# SCH_HOME-AUTOMATION_2025-03-31.net
KiCad netlist of a schematic drawn in EasyEDA
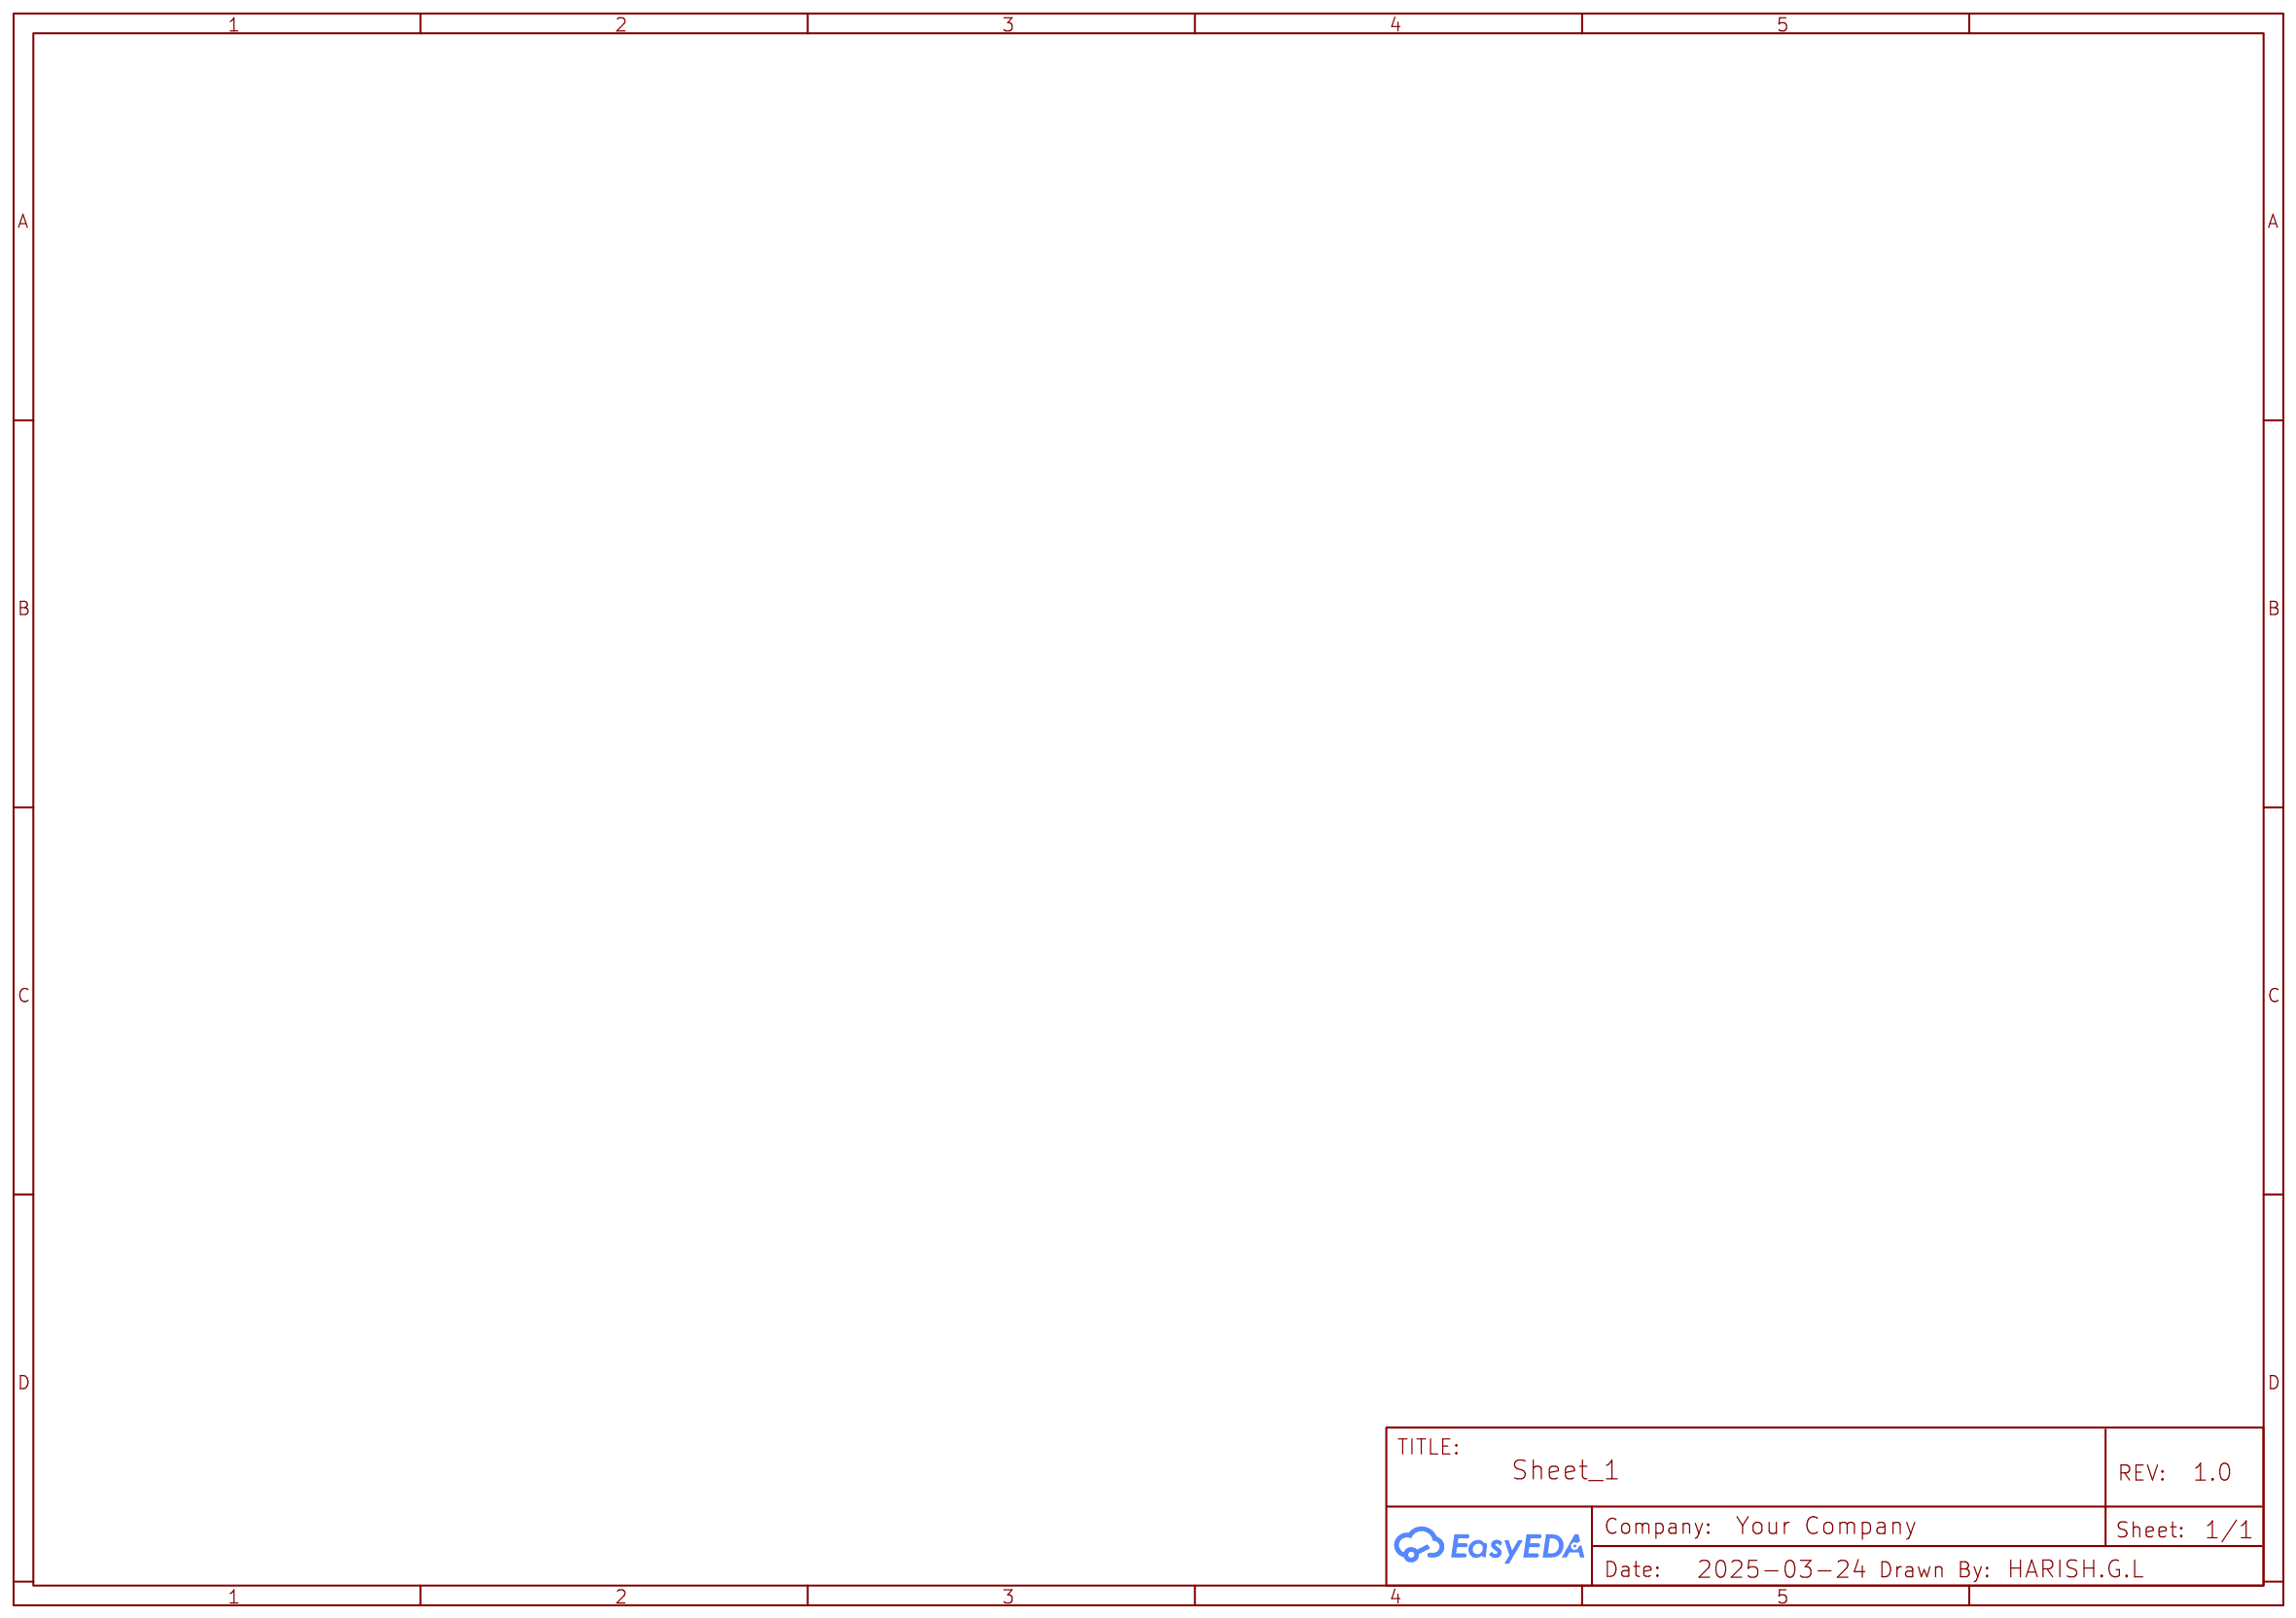
[diagram p0: Sheet_1]
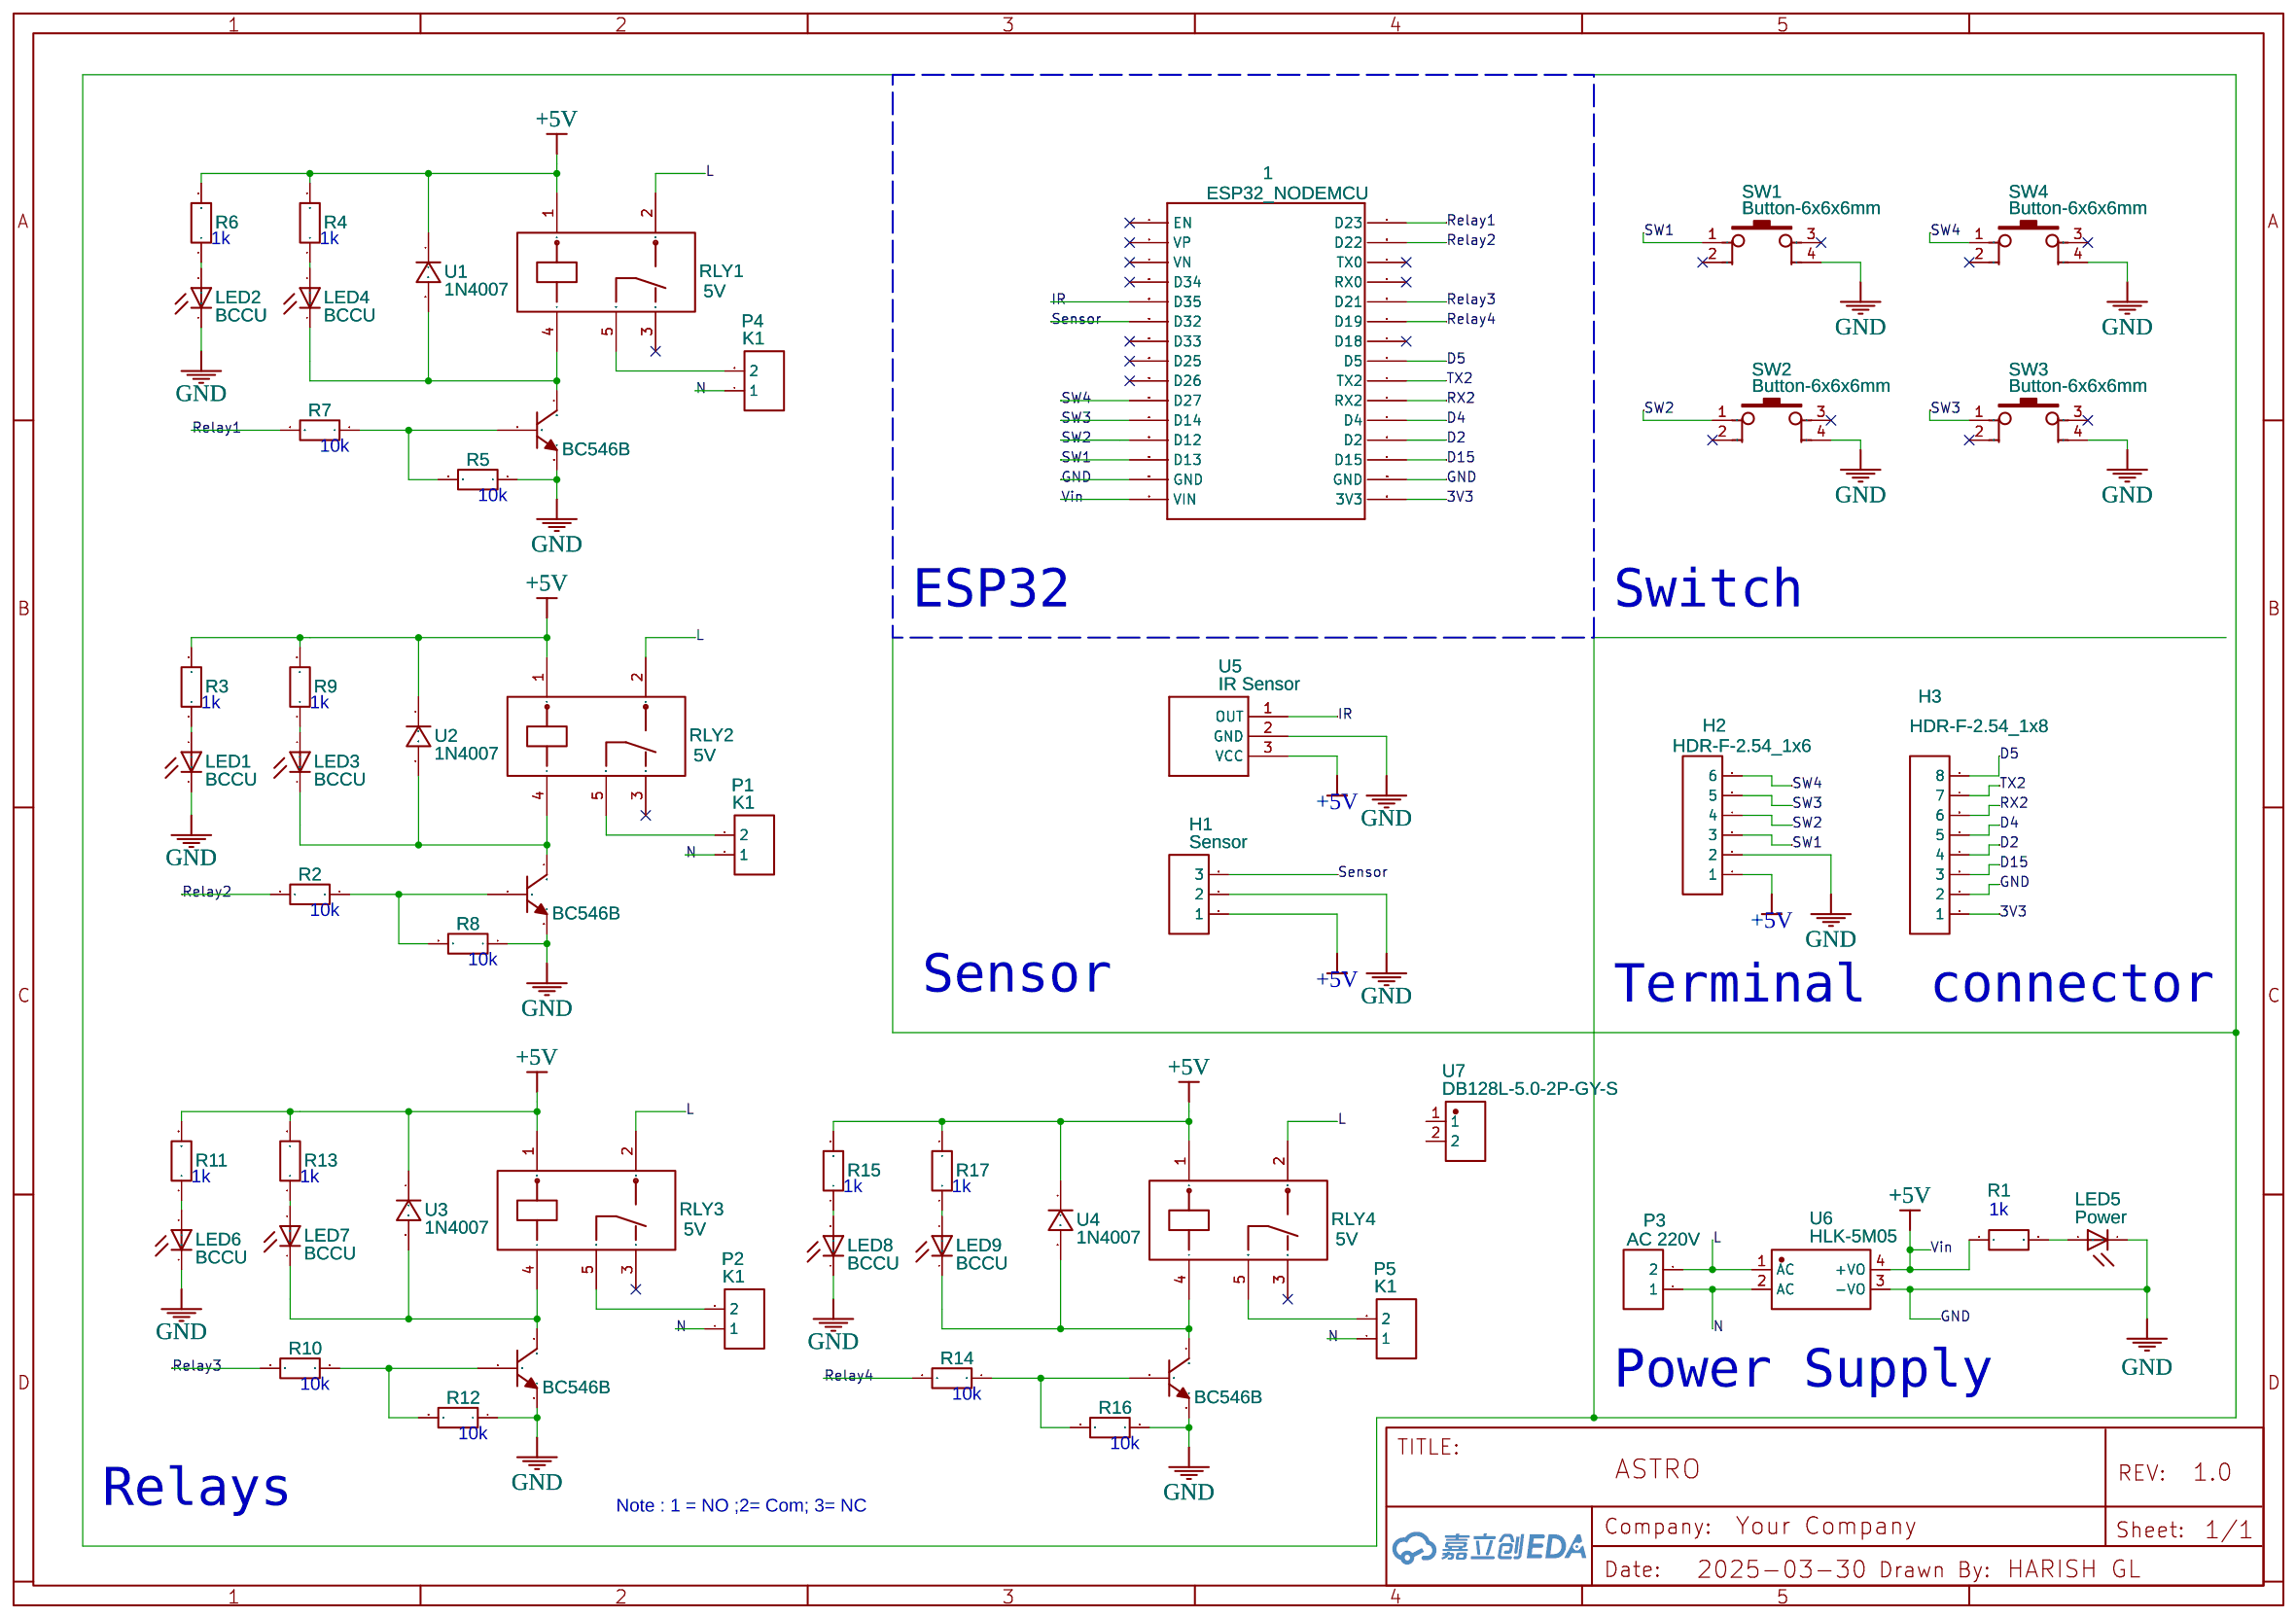
[diagram p1: ASTRO]

(export (version "E")
  (design (tool "Eeschema 10.0.6"))
  (components
    (comp (ref "1")
      (value "ESP32_NODEMCU")
      (libsource (lib "") (part "ESP32_NODEMCU_SHIELDESP32_NODEMCU_SHIELD_NOHOLES COPY"))
    )
    (comp (ref "C1") (value "BC546B") (libsource (lib "") (part "BC546B")))
    (comp (ref "C2") (value "BC546B") (libsource (lib "") (part "BC546B")))
    (comp (ref "C3") (value "BC546B") (libsource (lib "") (part "BC546B")))
    (comp (ref "C4") (value "BC546B") (libsource (lib "") (part "BC546B")))
    (comp (ref "H1") (value "Sensor") (libsource (lib "") (part "HDR-F-2.54_1x3")))
    (comp (ref "H2") (value "HDR-F-2.54_1x6") (libsource (lib "") (part "HDR-F-2.54_1x6")))
    (comp (ref "H3") (value "HDR-F-2.54_1x8") (libsource (lib "") (part "HDR-F-2.54_1x8")))
    (comp (ref "LED1") (value "BCCU") (libsource (lib "") (part "LED_LED5MM COPY2 COPY COPY_1")))
    (comp (ref "LED2") (value "BCCU") (libsource (lib "") (part "LED_LED5MM COPY2 COPY COPY_1")))
    (comp (ref "LED3") (value "BCCU") (libsource (lib "") (part "LED_LED5MM COPY2 COPY COPY_1")))
    (comp (ref "LED4") (value "BCCU") (libsource (lib "") (part "LED_LED5MM COPY2 COPY COPY_1")))
    (comp (ref "LED5") (value "Power") (libsource (lib "") (part "LED_LED5MM COPY2 COPY COPY")))
    (comp (ref "LED6") (value "BCCU") (libsource (lib "") (part "LED_LED5MM COPY2 COPY COPY_1")))
    (comp (ref "LED7") (value "BCCU") (libsource (lib "") (part "LED_LED5MM COPY2 COPY COPY_1")))
    (comp (ref "LED8") (value "BCCU") (libsource (lib "") (part "LED_LED5MM COPY2 COPY COPY_1")))
    (comp (ref "LED9") (value "BCCU") (libsource (lib "") (part "LED_LED5MM COPY2 COPY COPY_1")))
    (comp (ref "P1") (value "K1") (libsource (lib "") (part "CONN-TH_2P-P5.00")))
    (comp (ref "P2") (value "K1") (libsource (lib "") (part "CONN-TH_2P-P5.00")))
    (comp (ref "P3") (value "AC 220V") (libsource (lib "") (part "CONN-TH_2P-P5.00_1")))
    (comp (ref "P4") (value "K1") (libsource (lib "") (part "CONN-TH_2P-P5.00")))
    (comp (ref "P5") (value "K1") (libsource (lib "") (part "CONN-TH_2P-P5.00")))
    (comp (ref "R1") (value "RESISTOR1/4W COPY COPY") (libsource (lib "") (part "RESISTOR1/4W COPY COPY_2")))
    (comp (ref "R2") (value "RESISTOR1/4W COPY COPY") (libsource (lib "") (part "RESISTOR1/4W COPY COPY_1")))
    (comp (ref "R3") (value "RESISTOR1/4W COPY COPY") (libsource (lib "") (part "RESISTOR1/4W COPY COPY")))
    (comp (ref "R4") (value "RESISTOR1/4W COPY COPY") (libsource (lib "") (part "RESISTOR1/4W COPY COPY")))
    (comp (ref "R5") (value "RESISTOR1/4W COPY COPY") (libsource (lib "") (part "RESISTOR1/4W COPY COPY_1")))
    (comp (ref "R6") (value "RESISTOR1/4W COPY COPY") (libsource (lib "") (part "RESISTOR1/4W COPY COPY")))
    (comp (ref "R7") (value "RESISTOR1/4W COPY COPY") (libsource (lib "") (part "RESISTOR1/4W COPY COPY_1")))
    (comp (ref "R8") (value "RESISTOR1/4W COPY COPY") (libsource (lib "") (part "RESISTOR1/4W COPY COPY_1")))
    (comp (ref "R9") (value "RESISTOR1/4W COPY COPY") (libsource (lib "") (part "RESISTOR1/4W COPY COPY")))
    (comp (ref "R10") (value "RESISTOR1/4W COPY COPY") (libsource (lib "") (part "RESISTOR1/4W COPY COPY_1")))
    (comp (ref "R11") (value "RESISTOR1/4W COPY COPY") (libsource (lib "") (part "RESISTOR1/4W COPY COPY")))
    (comp (ref "R12") (value "RESISTOR1/4W COPY COPY") (libsource (lib "") (part "RESISTOR1/4W COPY COPY_1")))
    (comp (ref "R13") (value "RESISTOR1/4W COPY COPY") (libsource (lib "") (part "RESISTOR1/4W COPY COPY")))
    (comp (ref "R14") (value "RESISTOR1/4W COPY COPY") (libsource (lib "") (part "RESISTOR1/4W COPY COPY_1")))
    (comp (ref "R15") (value "RESISTOR1/4W COPY COPY") (libsource (lib "") (part "RESISTOR1/4W COPY COPY")))
    (comp (ref "R16") (value "RESISTOR1/4W COPY COPY") (libsource (lib "") (part "RESISTOR1/4W COPY COPY_1")))
    (comp (ref "R17") (value "RESISTOR1/4W COPY COPY") (libsource (lib "") (part "RESISTOR1/4W COPY COPY")))
    (comp (ref "RLY1")
      (value "5V")
      (fields (field (name "Manufacturer Part") "SRD-05VDC-SL-C") (field (name "Manufacturer") "SONGLE"))
      (libsource (lib "") (part "SRD-05VDC-SL-C"))
    )
    (comp (ref "RLY2")
      (value "5V")
      (fields (field (name "Manufacturer Part") "SRD-05VDC-SL-C") (field (name "Manufacturer") "SONGLE"))
      (libsource (lib "") (part "SRD-05VDC-SL-C"))
    )
    (comp (ref "RLY3")
      (value "5V")
      (fields (field (name "Manufacturer Part") "SRD-05VDC-SL-C") (field (name "Manufacturer") "SONGLE"))
      (libsource (lib "") (part "SRD-05VDC-SL-C"))
    )
    (comp (ref "RLY4")
      (value "5V")
      (fields (field (name "Manufacturer Part") "SRD-05VDC-SL-C") (field (name "Manufacturer") "SONGLE"))
      (libsource (lib "") (part "SRD-05VDC-SL-C"))
    )
    (comp (ref "SW1")
      (value "Button-6x6x6mm")
      (fields
        (field (name "Manufacturer Part") "Switch,6*6*6Plastic head,260G, 0.25mm,Straight line")
        (field (name "Manufacturer") "BBJ")
      )
      (libsource (lib "") (part "Button-6x6x6mm"))
    )
    (comp (ref "SW2")
      (value "Button-6x6x6mm")
      (fields
        (field (name "Manufacturer Part") "Switch,6*6*6Plastic head,260G, 0.25mm,Straight line")
        (field (name "Manufacturer") "BBJ")
      )
      (libsource (lib "") (part "Button-6x6x6mm"))
    )
    (comp (ref "SW3")
      (value "Button-6x6x6mm")
      (fields
        (field (name "Manufacturer Part") "Switch,6*6*6Plastic head,260G, 0.25mm,Straight line")
        (field (name "Manufacturer") "BBJ")
      )
      (libsource (lib "") (part "Button-6x6x6mm"))
    )
    (comp (ref "SW4")
      (value "Button-6x6x6mm")
      (fields
        (field (name "Manufacturer Part") "Switch,6*6*6Plastic head,260G, 0.25mm,Straight line")
        (field (name "Manufacturer") "BBJ")
      )
      (libsource (lib "") (part "Button-6x6x6mm"))
    )
    (comp (ref "U1") (value "1N4007") (libsource (lib "") (part "1N4007_SB")))
    (comp (ref "U2") (value "1N4007") (libsource (lib "") (part "1N4007_SB")))
    (comp (ref "U3") (value "1N4007") (libsource (lib "") (part "1N4007_SB")))
    (comp (ref "U4") (value "1N4007") (libsource (lib "") (part "1N4007_SB")))
    (comp (ref "U5") (value "IR Sensor") (libsource (lib "") (part "BRM-2A18RA")))
    (comp (ref "U6")
      (value "HLK-5M05")
      (fields (field (name "Manufacturer") "HI-LINK(海凌科)"))
      (libsource (lib "") (part "HLK-5M05"))
    )
    (comp (ref "U7")
      (value "DB128L-5.0-2P-GY-S")
      (fields (field (name "Manufacturer") "DIBO(地博电气)"))
      (libsource (lib "") (part "DB128L-5.0-2P-GY-S"))
    )
  )
  (nets
    (net (code "1") (name "3V3") (class "Default")
      (node (ref "1") (pin "3V3") (pinfunction "3V3_3V3") (pintype "bidirectional"))
      (node (ref "H3") (pin "1") (pinfunction "1_1") (pintype "unspecified"))
    )
    (net (code "2") (name "D2") (class "Default")
      (node (ref "1") (pin "D2") (pinfunction "D2_D2") (pintype "bidirectional"))
      (node (ref "H3") (pin "4") (pinfunction "4_4") (pintype "unspecified"))
    )
    (net (code "3") (name "D4") (class "Default")
      (node (ref "1") (pin "D4") (pinfunction "D4_D4") (pintype "bidirectional"))
      (node (ref "H3") (pin "5") (pinfunction "5_5") (pintype "unspecified"))
    )
    (net (code "4") (name "D5") (class "Default")
      (node (ref "1") (pin "D5") (pinfunction "D5_D5") (pintype "bidirectional"))
      (node (ref "H3") (pin "8") (pinfunction "8_8") (pintype "unspecified"))
    )
    (net (code "5") (name "D15") (class "Default")
      (node (ref "1") (pin "D15") (pinfunction "D15_D15") (pintype "bidirectional"))
      (node (ref "H3") (pin "3") (pinfunction "3_3") (pintype "unspecified"))
    )
    (net (code "6") (name "GND") (class "Default")
      (node (ref "1") (pin "GND@1") (pinfunction "GND_GND@1") (pintype "bidirectional"))
      (node (ref "1") (pin "GND@2") (pinfunction "GND_GND@2") (pintype "bidirectional"))
      (node (ref "C1") (pin "3") (pinfunction "E_3") (pintype "unspecified"))
      (node (ref "C2") (pin "3") (pinfunction "E_3") (pintype "unspecified"))
      (node (ref "C3") (pin "3") (pinfunction "E_3") (pintype "unspecified"))
      (node (ref "C4") (pin "3") (pinfunction "E_3") (pintype "unspecified"))
      (node (ref "H1") (pin "2") (pinfunction "2_2") (pintype "input"))
      (node (ref "H2") (pin "2") (pinfunction "2_2") (pintype "input"))
      (node (ref "H3") (pin "2") (pinfunction "2_2") (pintype "unspecified"))
      (node (ref "LED1") (pin "K") (pinfunction "C_K") (pintype "unspecified"))
      (node (ref "LED2") (pin "K") (pinfunction "C_K") (pintype "unspecified"))
      (node (ref "LED5") (pin "K") (pinfunction "C_K") (pintype "unspecified"))
      (node (ref "LED6") (pin "K") (pinfunction "C_K") (pintype "unspecified"))
      (node (ref "LED8") (pin "K") (pinfunction "C_K") (pintype "unspecified"))
      (node (ref "R12") (pin "1") (pinfunction "1_1") (pintype "unspecified"))
      (node (ref "R16") (pin "1") (pinfunction "1_1") (pintype "unspecified"))
      (node (ref "R5") (pin "1") (pinfunction "1_1") (pintype "unspecified"))
      (node (ref "R8") (pin "1") (pinfunction "1_1") (pintype "unspecified"))
      (node (ref "SW1") (pin "4") (pinfunction "4_4") (pintype "input"))
      (node (ref "SW2") (pin "4") (pinfunction "4_4") (pintype "input"))
      (node (ref "SW3") (pin "4") (pinfunction "4_4") (pintype "input"))
      (node (ref "SW4") (pin "4") (pinfunction "4_4") (pintype "input"))
      (node (ref "U5") (pin "2") (pinfunction "GND_2") (pintype "unspecified"))
      (node (ref "U6") (pin "3") (pinfunction "-VO_3") (pintype "unspecified"))
    )
    (net (code "7") (name "IR") (class "Default")
      (node (ref "1") (pin "D35") (pinfunction "D35_D35") (pintype "bidirectional"))
      (node (ref "U5") (pin "1") (pinfunction "OUT_1") (pintype "unspecified"))
    )
    (net (code "8") (name "L") (class "Default")
      (node (ref "P3") (pin "2") (pinfunction "2_2") (pintype "unspecified"))
      (node (ref "RLY1") (pin "2") (pinfunction "2_2") (pintype "input"))
      (node (ref "RLY2") (pin "2") (pinfunction "2_2") (pintype "input"))
      (node (ref "RLY3") (pin "2") (pinfunction "2_2") (pintype "input"))
      (node (ref "RLY4") (pin "2") (pinfunction "2_2") (pintype "input"))
      (node (ref "U6") (pin "1") (pinfunction "AC_1") (pintype "unspecified"))
    )
    (net (code "9") (name "N") (class "Default")
      (node (ref "P1") (pin "1") (pinfunction "1_1") (pintype "unspecified"))
      (node (ref "P2") (pin "1") (pinfunction "1_1") (pintype "unspecified"))
      (node (ref "P3") (pin "1") (pinfunction "1_1") (pintype "unspecified"))
      (node (ref "P4") (pin "1") (pinfunction "1_1") (pintype "unspecified"))
      (node (ref "P5") (pin "1") (pinfunction "1_1") (pintype "unspecified"))
      (node (ref "U6") (pin "2") (pinfunction "AC_2") (pintype "unspecified"))
    )
    (net (code "10") (name "Net-(C1-B)") (class "Default")
      (node (ref "C1") (pin "2") (pinfunction "B_2") (pintype "unspecified"))
      (node (ref "R5") (pin "2") (pinfunction "2_2") (pintype "unspecified"))
      (node (ref "R7") (pin "1") (pinfunction "1_1") (pintype "unspecified"))
    )
    (net (code "11") (name "Net-(C1-C)") (class "Default")
      (node (ref "C1") (pin "1") (pinfunction "C_1") (pintype "unspecified"))
      (node (ref "LED4") (pin "K") (pinfunction "C_K") (pintype "unspecified"))
      (node (ref "RLY1") (pin "4") (pinfunction "4_4") (pintype "input"))
      (node (ref "U1") (pin "2") (pinfunction "2_2") (pintype "unspecified"))
    )
    (net (code "12") (name "Net-(C2-B)") (class "Default")
      (node (ref "C2") (pin "2") (pinfunction "B_2") (pintype "unspecified"))
      (node (ref "R2") (pin "1") (pinfunction "1_1") (pintype "unspecified"))
      (node (ref "R8") (pin "2") (pinfunction "2_2") (pintype "unspecified"))
    )
    (net (code "13") (name "Net-(C2-C)") (class "Default")
      (node (ref "C2") (pin "1") (pinfunction "C_1") (pintype "unspecified"))
      (node (ref "LED3") (pin "K") (pinfunction "C_K") (pintype "unspecified"))
      (node (ref "RLY2") (pin "4") (pinfunction "4_4") (pintype "input"))
      (node (ref "U2") (pin "2") (pinfunction "2_2") (pintype "unspecified"))
    )
    (net (code "14") (name "Net-(C3-B)") (class "Default")
      (node (ref "C3") (pin "2") (pinfunction "B_2") (pintype "unspecified"))
      (node (ref "R10") (pin "1") (pinfunction "1_1") (pintype "unspecified"))
      (node (ref "R12") (pin "2") (pinfunction "2_2") (pintype "unspecified"))
    )
    (net (code "15") (name "Net-(C3-C)") (class "Default")
      (node (ref "C3") (pin "1") (pinfunction "C_1") (pintype "unspecified"))
      (node (ref "LED7") (pin "K") (pinfunction "C_K") (pintype "unspecified"))
      (node (ref "RLY3") (pin "4") (pinfunction "4_4") (pintype "input"))
      (node (ref "U3") (pin "2") (pinfunction "2_2") (pintype "unspecified"))
    )
    (net (code "16") (name "Net-(C4-B)") (class "Default")
      (node (ref "C4") (pin "2") (pinfunction "B_2") (pintype "unspecified"))
      (node (ref "R14") (pin "1") (pinfunction "1_1") (pintype "unspecified"))
      (node (ref "R16") (pin "2") (pinfunction "2_2") (pintype "unspecified"))
    )
    (net (code "17") (name "Net-(C4-C)") (class "Default")
      (node (ref "C4") (pin "1") (pinfunction "C_1") (pintype "unspecified"))
      (node (ref "LED9") (pin "K") (pinfunction "C_K") (pintype "unspecified"))
      (node (ref "RLY4") (pin "4") (pinfunction "4_4") (pintype "input"))
      (node (ref "U4") (pin "2") (pinfunction "2_2") (pintype "unspecified"))
    )
    (net (code "18") (name "Net-(LED1-PadA)") (class "Default")
      (node (ref "LED1") (pin "A") (pinfunction "A_A") (pintype "unspecified"))
      (node (ref "R3") (pin "1") (pinfunction "1_1") (pintype "unspecified"))
    )
    (net (code "19") (name "Net-(LED2-PadA)") (class "Default")
      (node (ref "LED2") (pin "A") (pinfunction "A_A") (pintype "unspecified"))
      (node (ref "R6") (pin "1") (pinfunction "1_1") (pintype "unspecified"))
    )
    (net (code "20") (name "Net-(LED3-PadA)") (class "Default")
      (node (ref "LED3") (pin "A") (pinfunction "A_A") (pintype "unspecified"))
      (node (ref "R9") (pin "1") (pinfunction "1_1") (pintype "unspecified"))
    )
    (net (code "21") (name "Net-(LED4-PadA)") (class "Default")
      (node (ref "LED4") (pin "A") (pinfunction "A_A") (pintype "unspecified"))
      (node (ref "R4") (pin "1") (pinfunction "1_1") (pintype "unspecified"))
    )
    (net (code "22") (name "Net-(LED5-PadA)") (class "Default")
      (node (ref "LED5") (pin "A") (pinfunction "A_A") (pintype "unspecified"))
      (node (ref "R1") (pin "2") (pinfunction "2_2") (pintype "unspecified"))
    )
    (net (code "23") (name "Net-(LED6-PadA)") (class "Default")
      (node (ref "LED6") (pin "A") (pinfunction "A_A") (pintype "unspecified"))
      (node (ref "R11") (pin "1") (pinfunction "1_1") (pintype "unspecified"))
    )
    (net (code "24") (name "Net-(LED7-PadA)") (class "Default")
      (node (ref "LED7") (pin "A") (pinfunction "A_A") (pintype "unspecified"))
      (node (ref "R13") (pin "1") (pinfunction "1_1") (pintype "unspecified"))
    )
    (net (code "25") (name "Net-(LED8-PadA)") (class "Default")
      (node (ref "LED8") (pin "A") (pinfunction "A_A") (pintype "unspecified"))
      (node (ref "R15") (pin "1") (pinfunction "1_1") (pintype "unspecified"))
    )
    (net (code "26") (name "Net-(LED9-PadA)") (class "Default")
      (node (ref "LED9") (pin "A") (pinfunction "A_A") (pintype "unspecified"))
      (node (ref "R17") (pin "1") (pinfunction "1_1") (pintype "unspecified"))
    )
    (net (code "27") (name "Net-(P1-Pad2)") (class "Default")
      (node (ref "P1") (pin "2") (pinfunction "2_2") (pintype "unspecified"))
      (node (ref "RLY2") (pin "5") (pinfunction "5_5") (pintype "input"))
    )
    (net (code "28") (name "Net-(P2-Pad2)") (class "Default")
      (node (ref "P2") (pin "2") (pinfunction "2_2") (pintype "unspecified"))
      (node (ref "RLY3") (pin "5") (pinfunction "5_5") (pintype "input"))
    )
    (net (code "29") (name "Net-(P4-Pad2)") (class "Default")
      (node (ref "P4") (pin "2") (pinfunction "2_2") (pintype "unspecified"))
      (node (ref "RLY1") (pin "5") (pinfunction "5_5") (pintype "input"))
    )
    (net (code "30") (name "Net-(P5-Pad2)") (class "Default")
      (node (ref "P5") (pin "2") (pinfunction "2_2") (pintype "unspecified"))
      (node (ref "RLY4") (pin "5") (pinfunction "5_5") (pintype "input"))
    )
    (net (code "31") (name "RX2") (class "Default")
      (node (ref "1") (pin "RX2") (pinfunction "RX2_RX2") (pintype "bidirectional"))
      (node (ref "H3") (pin "6") (pinfunction "6_6") (pintype "unspecified"))
    )
    (net (code "32") (name "Relay1") (class "Default")
      (node (ref "1") (pin "D23") (pinfunction "D23_D23") (pintype "bidirectional"))
      (node (ref "R7") (pin "2") (pinfunction "2_2") (pintype "unspecified"))
    )
    (net (code "33") (name "Relay2") (class "Default")
      (node (ref "1") (pin "D22") (pinfunction "D22_D22") (pintype "bidirectional"))
      (node (ref "R2") (pin "2") (pinfunction "2_2") (pintype "unspecified"))
    )
    (net (code "34") (name "Relay3") (class "Default")
      (node (ref "1") (pin "D21") (pinfunction "D21_D21") (pintype "bidirectional"))
      (node (ref "R10") (pin "2") (pinfunction "2_2") (pintype "unspecified"))
    )
    (net (code "35") (name "Relay4") (class "Default")
      (node (ref "1") (pin "D19") (pinfunction "D19_D19") (pintype "bidirectional"))
      (node (ref "R14") (pin "2") (pinfunction "2_2") (pintype "unspecified"))
    )
    (net (code "36") (name "SW1") (class "Default")
      (node (ref "1") (pin "D13") (pinfunction "D13_D13") (pintype "bidirectional"))
      (node (ref "H2") (pin "3") (pinfunction "3_3") (pintype "input"))
      (node (ref "SW1") (pin "1") (pinfunction "1_1") (pintype "input"))
    )
    (net (code "37") (name "SW2") (class "Default")
      (node (ref "1") (pin "D12") (pinfunction "D12_D12") (pintype "bidirectional"))
      (node (ref "H2") (pin "4") (pinfunction "4_4") (pintype "input"))
      (node (ref "SW2") (pin "1") (pinfunction "1_1") (pintype "input"))
    )
    (net (code "38") (name "SW3") (class "Default")
      (node (ref "1") (pin "D14") (pinfunction "D14_D14") (pintype "bidirectional"))
      (node (ref "H2") (pin "5") (pinfunction "5_5") (pintype "input"))
      (node (ref "SW3") (pin "1") (pinfunction "1_1") (pintype "input"))
    )
    (net (code "39") (name "SW4") (class "Default")
      (node (ref "1") (pin "D27") (pinfunction "D27_D27") (pintype "bidirectional"))
      (node (ref "H2") (pin "6") (pinfunction "6_6") (pintype "input"))
      (node (ref "SW4") (pin "1") (pinfunction "1_1") (pintype "input"))
    )
    (net (code "40") (name "Sensor") (class "Default")
      (node (ref "1") (pin "D32") (pinfunction "D32_D32") (pintype "bidirectional"))
      (node (ref "H1") (pin "3") (pinfunction "3_3") (pintype "input"))
    )
    (net (code "41") (name "TX2") (class "Default")
      (node (ref "1") (pin "TX2") (pinfunction "TX2_TX2") (pintype "bidirectional"))
      (node (ref "H3") (pin "7") (pinfunction "7_7") (pintype "unspecified"))
    )
    (net (code "42") (name "Vin") (class "Default")
      (node (ref "1") (pin "VIN") (pinfunction "VIN_VIN") (pintype "bidirectional"))
      (node (ref "H1") (pin "1") (pinfunction "1_1") (pintype "input"))
      (node (ref "H2") (pin "1") (pinfunction "1_1") (pintype "input"))
      (node (ref "R1") (pin "1") (pinfunction "1_1") (pintype "unspecified"))
      (node (ref "R11") (pin "2") (pinfunction "2_2") (pintype "unspecified"))
      (node (ref "R13") (pin "2") (pinfunction "2_2") (pintype "unspecified"))
      (node (ref "R15") (pin "2") (pinfunction "2_2") (pintype "unspecified"))
      (node (ref "R17") (pin "2") (pinfunction "2_2") (pintype "unspecified"))
      (node (ref "R3") (pin "2") (pinfunction "2_2") (pintype "unspecified"))
      (node (ref "R4") (pin "2") (pinfunction "2_2") (pintype "unspecified"))
      (node (ref "R6") (pin "2") (pinfunction "2_2") (pintype "unspecified"))
      (node (ref "R9") (pin "2") (pinfunction "2_2") (pintype "unspecified"))
      (node (ref "RLY1") (pin "1") (pinfunction "1_1") (pintype "input"))
      (node (ref "RLY2") (pin "1") (pinfunction "1_1") (pintype "input"))
      (node (ref "RLY3") (pin "1") (pinfunction "1_1") (pintype "input"))
      (node (ref "RLY4") (pin "1") (pinfunction "1_1") (pintype "input"))
      (node (ref "U1") (pin "1") (pinfunction "1_1") (pintype "unspecified"))
      (node (ref "U2") (pin "1") (pinfunction "1_1") (pintype "unspecified"))
      (node (ref "U3") (pin "1") (pinfunction "1_1") (pintype "unspecified"))
      (node (ref "U4") (pin "1") (pinfunction "1_1") (pintype "unspecified"))
      (node (ref "U5") (pin "3") (pinfunction "VCC_3") (pintype "unspecified"))
      (node (ref "U6") (pin "4") (pinfunction "+VO_4") (pintype "unspecified"))
    )
    (net (code "43") (name "unconnected-(1-PadD18)") (class "Default")
      (node (ref "1") (pin "D18") (pinfunction "D18_D18") (pintype "bidirectional+no_connect"))
    )
    (net (code "44") (name "unconnected-(1-PadD25)") (class "Default")
      (node (ref "1") (pin "D25") (pinfunction "D25_D25") (pintype "bidirectional+no_connect"))
    )
    (net (code "45") (name "unconnected-(1-PadD26)") (class "Default")
      (node (ref "1") (pin "D26") (pinfunction "D26_D26") (pintype "bidirectional+no_connect"))
    )
    (net (code "46") (name "unconnected-(1-PadD33)") (class "Default")
      (node (ref "1") (pin "D33") (pinfunction "D33_D33") (pintype "bidirectional+no_connect"))
    )
    (net (code "47") (name "unconnected-(1-PadD34)") (class "Default")
      (node (ref "1") (pin "D34") (pinfunction "D34_D34") (pintype "bidirectional+no_connect"))
    )
    (net (code "48") (name "unconnected-(1-PadEN)") (class "Default")
      (node (ref "1") (pin "EN") (pinfunction "EN_EN") (pintype "bidirectional+no_connect"))
    )
    (net (code "49") (name "unconnected-(1-PadRX0)") (class "Default")
      (node (ref "1") (pin "RX0") (pinfunction "RX0_RX0") (pintype "bidirectional+no_connect"))
    )
    (net (code "50") (name "unconnected-(1-PadTX0)") (class "Default")
      (node (ref "1") (pin "TX0") (pinfunction "TX0_TX0") (pintype "bidirectional+no_connect"))
    )
    (net (code "51") (name "unconnected-(1-PadVN)") (class "Default")
      (node (ref "1") (pin "VN") (pinfunction "VN_VN") (pintype "bidirectional+no_connect"))
    )
    (net (code "52") (name "unconnected-(1-PadVP)") (class "Default")
      (node (ref "1") (pin "VP") (pinfunction "VP_VP") (pintype "bidirectional+no_connect"))
    )
    (net (code "53") (name "unconnected-(RLY1-Pad3)") (class "Default")
      (node (ref "RLY1") (pin "3") (pinfunction "3_3") (pintype "input+no_connect"))
    )
    (net (code "54") (name "unconnected-(RLY2-Pad3)") (class "Default")
      (node (ref "RLY2") (pin "3") (pinfunction "3_3") (pintype "input+no_connect"))
    )
    (net (code "55") (name "unconnected-(RLY3-Pad3)") (class "Default")
      (node (ref "RLY3") (pin "3") (pinfunction "3_3") (pintype "input+no_connect"))
    )
    (net (code "56") (name "unconnected-(RLY4-Pad3)") (class "Default")
      (node (ref "RLY4") (pin "3") (pinfunction "3_3") (pintype "input+no_connect"))
    )
    (net (code "57") (name "unconnected-(SW1-Pad2)") (class "Default")
      (node (ref "SW1") (pin "2") (pinfunction "2_2") (pintype "input+no_connect"))
    )
    (net (code "58") (name "unconnected-(SW1-Pad3)") (class "Default")
      (node (ref "SW1") (pin "3") (pinfunction "3_3") (pintype "input+no_connect"))
    )
    (net (code "59") (name "unconnected-(SW2-Pad2)") (class "Default")
      (node (ref "SW2") (pin "2") (pinfunction "2_2") (pintype "input+no_connect"))
    )
    (net (code "60") (name "unconnected-(SW2-Pad3)") (class "Default")
      (node (ref "SW2") (pin "3") (pinfunction "3_3") (pintype "input+no_connect"))
    )
    (net (code "61") (name "unconnected-(SW3-Pad2)") (class "Default")
      (node (ref "SW3") (pin "2") (pinfunction "2_2") (pintype "input+no_connect"))
    )
    (net (code "62") (name "unconnected-(SW3-Pad3)") (class "Default")
      (node (ref "SW3") (pin "3") (pinfunction "3_3") (pintype "input+no_connect"))
    )
    (net (code "63") (name "unconnected-(SW4-Pad2)") (class "Default")
      (node (ref "SW4") (pin "2") (pinfunction "2_2") (pintype "input+no_connect"))
    )
    (net (code "64") (name "unconnected-(SW4-Pad3)") (class "Default")
      (node (ref "SW4") (pin "3") (pinfunction "3_3") (pintype "input+no_connect"))
    )
    (net (code "65") (name "unconnected-(U7-Pad1)") (class "Default")
      (node (ref "U7") (pin "1") (pinfunction "1_1") (pintype "unspecified"))
    )
    (net (code "66") (name "unconnected-(U7-Pad2)") (class "Default")
      (node (ref "U7") (pin "2") (pinfunction "2_2") (pintype "unspecified"))
    )
  )
)
